# tinyi2c.net
KiCad netlist of a schematic drawn in EAGLE
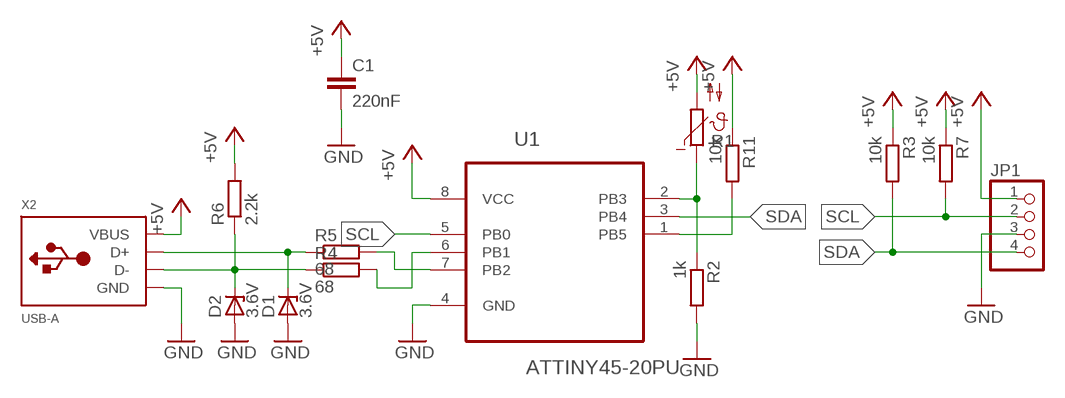
[diagram p0: schematic, sheet 1]

(export (version "E")
  (design (tool "Eeschema 10.0.6"))
  (components
    (comp (ref "C1")
      (value "220nF")
      (footprint "eagle-import:C075-032X103")
      (libsource (lib "eagle-import") (part "C-EU075-032X103"))
    )
    (comp (ref "D1")
      (value "3.6V")
      (footprint "eagle-import:ZDIO-2.5")
      (libsource (lib "eagle-import") (part "ZENER-DIODEZD-2.5"))
    )
    (comp (ref "D2")
      (value "3.6V")
      (footprint "eagle-import:ZDIO-5")
      (libsource (lib "eagle-import") (part "ZENER-DIODEZD-5"))
    )
    (comp (ref "JP1")
      (value "PINHD-1X4")
      (footprint "eagle-import:1X04")
      (libsource (lib "eagle-import") (part "PINHD-1X4"))
    )
    (comp (ref "R1")
      (value "B57164")
      (footprint "eagle-import:B57164")
      (fields (field (name "MPN") "B57164K474K52"))
      (libsource (lib "eagle-import") (part "B57164"))
    )
    (comp (ref "R2")
      (value "1k")
      (footprint "eagle-import:0207_10")
      (libsource (lib "eagle-import") (part "R-EU_0207/10"))
    )
    (comp (ref "R3")
      (value "10k")
      (footprint "eagle-import:0207_10")
      (libsource (lib "eagle-import") (part "R-EU_0207/10"))
    )
    (comp (ref "R4")
      (value "68")
      (footprint "eagle-import:0204_5")
      (libsource (lib "eagle-import") (part "R-EU_0204/5"))
    )
    (comp (ref "R5")
      (value "68")
      (footprint "eagle-import:0204_5")
      (libsource (lib "eagle-import") (part "R-EU_0204/5"))
    )
    (comp (ref "R6")
      (value "2.2k")
      (footprint "eagle-import:0204V")
      (libsource (lib "eagle-import") (part "R-EU_0204/2V"))
    )
    (comp (ref "R7")
      (value "10k")
      (footprint "eagle-import:0204V")
      (libsource (lib "eagle-import") (part "R-EU_0204/2V"))
    )
    (comp (ref "R11")
      (value "10k")
      (footprint "eagle-import:0204_7")
      (libsource (lib "eagle-import") (part "R-EU_0204/7"))
    )
    (comp (ref "U1")
      (value "ATTINY45-20PU")
      (footprint "eagle-import:DIP254P762X533-8")
      (libsource (lib "eagle-import") (part "ATTINY45-20PU"))
    )
    (comp (ref "X2")
      (value "USB-A")
      (footprint "eagle-import:MOLEX_480371000")
      (libsource (lib "eagle-import") (part "USB-A"))
    )
  )
  (nets
    (net (code "1") (name "+5V") (class "Default")
      (node (ref "C1") (pin "1") (pinfunction "1_1") (pintype "passive"))
      (node (ref "JP1") (pin "1") (pinfunction "1_1") (pintype "passive"))
      (node (ref "R1") (pin "2") (pinfunction "2_2") (pintype "passive"))
      (node (ref "R11") (pin "1") (pinfunction "1_1") (pintype "passive"))
      (node (ref "R3") (pin "1") (pinfunction "1_1") (pintype "passive"))
      (node (ref "R6") (pin "2") (pinfunction "2_2") (pintype "passive"))
      (node (ref "R7") (pin "1") (pinfunction "1_1") (pintype "passive"))
      (node (ref "U1") (pin "8") (pinfunction "VCC_8") (pintype "power_in"))
      (node (ref "X2") (pin "1") (pinfunction "VBUS_1") (pintype "power_in"))
    )
    (net (code "2") (name "GND") (class "Default")
      (node (ref "C1") (pin "2") (pinfunction "2_2") (pintype "passive"))
      (node (ref "D1") (pin "A") (pinfunction "A_A") (pintype "passive"))
      (node (ref "D2") (pin "A") (pinfunction "A_A") (pintype "passive"))
      (node (ref "JP1") (pin "3") (pinfunction "3_3") (pintype "passive"))
      (node (ref "R2") (pin "2") (pinfunction "2_2") (pintype "passive"))
      (node (ref "U1") (pin "4") (pinfunction "GND_4") (pintype "passive"))
      (node (ref "X2") (pin "4") (pinfunction "GND_4") (pintype "power_in"))
    )
    (net (code "3") (name "Net-(U1-PB1)") (class "Default")
      (node (ref "R4") (pin "2") (pinfunction "2_2") (pintype "passive"))
      (node (ref "U1") (pin "6") (pinfunction "PB1_6") (pintype "bidirectional"))
    )
    (net (code "4") (name "Net-(U1-PB2)") (class "Default")
      (node (ref "R5") (pin "2") (pinfunction "2_2") (pintype "passive"))
      (node (ref "U1") (pin "7") (pinfunction "PB2_7") (pintype "bidirectional"))
    )
    (net (code "5") (name "Net-(U1-PB3)") (class "Default")
      (node (ref "R1") (pin "1") (pinfunction "1_1") (pintype "passive"))
      (node (ref "R2") (pin "1") (pinfunction "1_1") (pintype "passive"))
      (node (ref "U1") (pin "2") (pinfunction "PB3_2") (pintype "bidirectional"))
    )
    (net (code "6") (name "Net-(U1-PB5)") (class "Default")
      (node (ref "R11") (pin "2") (pinfunction "2_2") (pintype "passive"))
      (node (ref "U1") (pin "1") (pinfunction "PB5_1") (pintype "bidirectional"))
    )
    (net (code "7") (name "Net-(X2-D+)") (class "Default")
      (node (ref "D1") (pin "C") (pinfunction "C_C") (pintype "passive"))
      (node (ref "R5") (pin "1") (pinfunction "1_1") (pintype "passive"))
      (node (ref "X2") (pin "3") (pinfunction "D+_3") (pintype "bidirectional"))
    )
    (net (code "8") (name "Net-(X2-D-)") (class "Default")
      (node (ref "D2") (pin "C") (pinfunction "C_C") (pintype "passive"))
      (node (ref "R4") (pin "1") (pinfunction "1_1") (pintype "passive"))
      (node (ref "R6") (pin "1") (pinfunction "1_1") (pintype "passive"))
      (node (ref "X2") (pin "2") (pinfunction "D-_2") (pintype "bidirectional"))
    )
    (net (code "9") (name "SCL") (class "Default")
      (node (ref "JP1") (pin "2") (pinfunction "2_2") (pintype "passive"))
      (node (ref "R7") (pin "2") (pinfunction "2_2") (pintype "passive"))
      (node (ref "U1") (pin "5") (pinfunction "PB0_5") (pintype "bidirectional"))
    )
    (net (code "10") (name "SDA") (class "Default")
      (node (ref "JP1") (pin "4") (pinfunction "4_4") (pintype "passive"))
      (node (ref "R3") (pin "2") (pinfunction "2_2") (pintype "passive"))
      (node (ref "U1") (pin "3") (pinfunction "PB4_3") (pintype "bidirectional"))
    )
  )
)
